# potencia.net
KiCad netlist of a schematic drawn in EAGLE
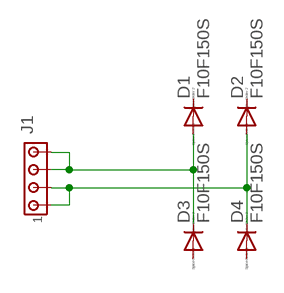
[diagram p0: schematic, sheet 1]

(export (version "E")
  (design (tool "Eeschema 10.0.6"))
  (components
    (comp (ref "D1")
      (value "F10F150S")
      (footprint "eagle-import:DO220S")
      (libsource (lib "eagle-import") (part "FES08AT"))
    )
    (comp (ref "D2")
      (value "F10F150S")
      (footprint "eagle-import:DO220S")
      (libsource (lib "eagle-import") (part "FES08AT"))
    )
    (comp (ref "D3")
      (value "F10F150S")
      (footprint "eagle-import:DO220S")
      (libsource (lib "eagle-import") (part "FES08AT"))
    )
    (comp (ref "D4")
      (value "F10F150S")
      (footprint "eagle-import:DO220S")
      (libsource (lib "eagle-import") (part "FES08AT"))
    )
    (comp (ref "J1")
      (value "MTA04-156")
      (footprint "eagle-import:1X4MTA")
      (libsource (lib "eagle-import") (part "MTA04-156"))
    )
  )
  (nets
    (net (code "1") (name "Net-(D1-PadA)") (class "Default")
      (node (ref "D1") (pin "A") (pinfunction "A_A") (pintype "passive"))
      (node (ref "D3") (pin "C") (pinfunction "C_C") (pintype "passive"))
      (node (ref "J1") (pin "3") (pinfunction "3_3") (pintype "passive"))
      (node (ref "J1") (pin "4") (pinfunction "4_4") (pintype "passive"))
    )
    (net (code "2") (name "Net-(D2-PadA)") (class "Default")
      (node (ref "D2") (pin "A") (pinfunction "A_A") (pintype "passive"))
      (node (ref "D4") (pin "C") (pinfunction "C_C") (pintype "passive"))
      (node (ref "J1") (pin "1") (pinfunction "1_1") (pintype "passive"))
      (node (ref "J1") (pin "2") (pinfunction "2_2") (pintype "passive"))
    )
    (net (code "3") (name "unconnected-(D1-PadC)") (class "Default")
      (node (ref "D1") (pin "C") (pinfunction "C_C") (pintype "passive"))
    )
    (net (code "4") (name "unconnected-(D2-PadC)") (class "Default")
      (node (ref "D2") (pin "C") (pinfunction "C_C") (pintype "passive"))
    )
    (net (code "5") (name "unconnected-(D3-PadA)") (class "Default")
      (node (ref "D3") (pin "A") (pinfunction "A_A") (pintype "passive"))
    )
    (net (code "6") (name "unconnected-(D4-PadA)") (class "Default")
      (node (ref "D4") (pin "A") (pinfunction "A_A") (pintype "passive"))
    )
  )
)
